# NFC_Access_NFC_Reader_R00.net
KiCad netlist of a schematic drawn in Altium Designer
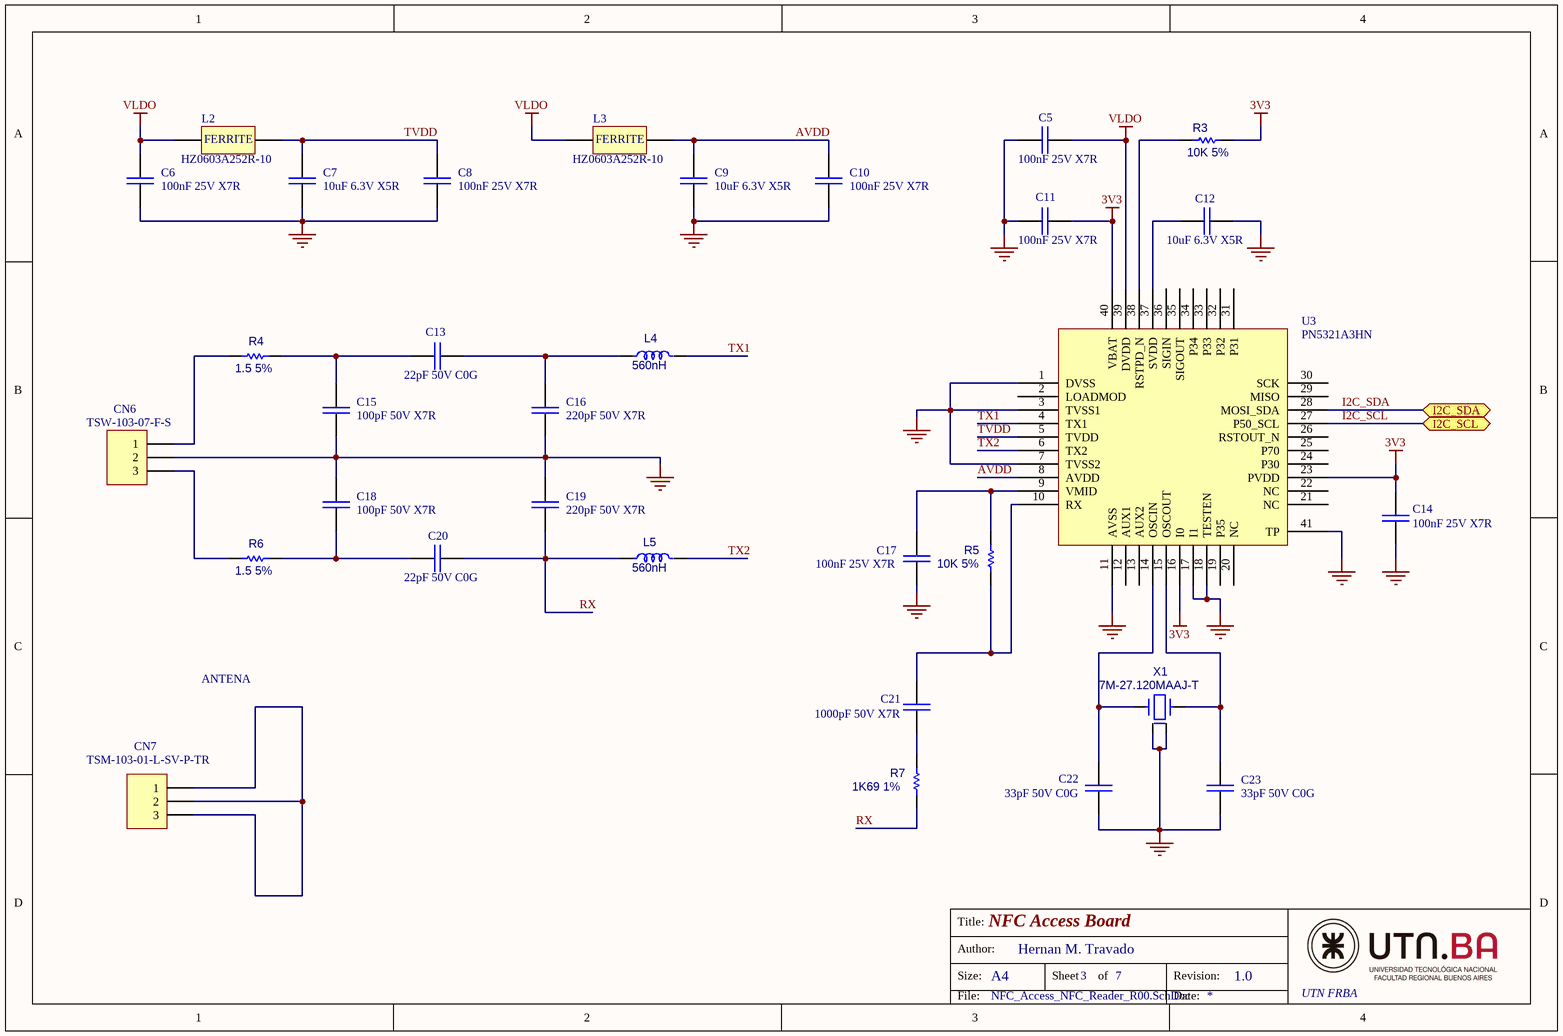
[diagram p0: NFC_Access_NFC_Reader_R00.SchDoc]

(export (version "E")
  (design (tool "Eeschema 10.0.6"))
  (components
    (comp (ref "C5")
      (value "100nF 25V X7R")
      (footprint "C_0603")
      (description "Ceramic Capacitor\r\n1276-1018-2-ND")
      (libsource (lib "NFC_Access_Lib") (part "Ceramic capacitor"))
    )
    (comp (ref "C6")
      (value "100nF 25V X7R")
      (footprint "C_0603")
      (description "Ceramic Capacitor\r\n1276-1018-2-ND")
      (libsource (lib "NFC_Access_Lib") (part "Ceramic capacitor"))
    )
    (comp (ref "C7")
      (value "10uF 6.3V X5R")
      (footprint "C_0603")
      (description "Ceramic Capacitor\r\n1276-1119-2-ND")
      (libsource (lib "NFC_Access_Lib") (part "Ceramic capacitor"))
    )
    (comp (ref "C8")
      (value "100nF 25V X7R")
      (footprint "C_0603")
      (description "Ceramic Capacitor\r\n1276-1018-2-ND")
      (libsource (lib "NFC_Access_Lib") (part "Ceramic capacitor"))
    )
    (comp (ref "C9")
      (value "10uF 6.3V X5R")
      (footprint "C_0603")
      (description "Ceramic Capacitor\r\n1276-1119-2-ND")
      (libsource (lib "NFC_Access_Lib") (part "Ceramic capacitor"))
    )
    (comp (ref "C10")
      (value "100nF 25V X7R")
      (footprint "C_0603")
      (description "Ceramic Capacitor\r\n1276-1018-2-ND")
      (libsource (lib "NFC_Access_Lib") (part "Ceramic capacitor"))
    )
    (comp (ref "C11")
      (value "100nF 25V X7R")
      (footprint "C_0603")
      (description "Ceramic Capacitor\r\n1276-1018-2-ND")
      (libsource (lib "NFC_Access_Lib") (part "Ceramic capacitor"))
    )
    (comp (ref "C12")
      (value "10uF 6.3V X5R")
      (footprint "C_0603")
      (description "Ceramic Capacitor\r\n1276-1119-2-ND")
      (libsource (lib "NFC_Access_Lib") (part "Ceramic capacitor"))
    )
    (comp (ref "C13")
      (value "22pF 50V C0G")
      (footprint "C_0603")
      (description "Ceramic Capacitor\r\n1276-2228-2-ND")
      (libsource (lib "NFC_Access_Lib") (part "Ceramic capacitor"))
    )
    (comp (ref "C14")
      (value "100nF 25V X7R")
      (footprint "C_0603")
      (description "Ceramic Capacitor\r\n1276-1018-2-ND")
      (libsource (lib "NFC_Access_Lib") (part "Ceramic capacitor"))
    )
    (comp (ref "C15")
      (value "100pF 50V X7R")
      (footprint "C_0603")
      (description "Ceramic Capacitor\r\n1276-1908-2-ND")
      (libsource (lib "NFC_Access_Lib") (part "Ceramic capacitor"))
    )
    (comp (ref "C16")
      (value "220pF 50V X7R")
      (footprint "C_0603")
      (description "Ceramic Capacitor\r\n1276-1986-2-ND")
      (libsource (lib "NFC_Access_Lib") (part "Ceramic capacitor"))
    )
    (comp (ref "C17")
      (value "100nF 25V X7R")
      (footprint "C_0603")
      (description "Ceramic Capacitor\r\n1276-1018-2-ND")
      (libsource (lib "NFC_Access_Lib") (part "Ceramic capacitor"))
    )
    (comp (ref "C18")
      (value "100pF 50V X7R")
      (footprint "C_0603")
      (description "Ceramic Capacitor\r\n1276-1908-2-ND")
      (libsource (lib "NFC_Access_Lib") (part "Ceramic capacitor"))
    )
    (comp (ref "C19")
      (value "220pF 50V X7R")
      (footprint "C_0603")
      (description "Ceramic Capacitor\r\n1276-1986-2-ND")
      (libsource (lib "NFC_Access_Lib") (part "Ceramic capacitor"))
    )
    (comp (ref "C20")
      (value "22pF 50V C0G")
      (footprint "C_0603")
      (description "Ceramic Capacitor\r\n1276-2228-2-ND")
      (libsource (lib "NFC_Access_Lib") (part "Ceramic capacitor"))
    )
    (comp (ref "C21")
      (value "1000pF 50V X7R")
      (footprint "C_0603")
      (description "Ceramic Capacitor\r\n1276-1018-2-ND")
      (libsource (lib "NFC_Access_Lib") (part "Ceramic capacitor"))
    )
    (comp (ref "C22")
      (value "33pF 50V C0G")
      (footprint "C_0603")
      (description "Ceramic Capacitor\r\n1276-1070-2-ND")
      (libsource (lib "NFC_Access_Lib") (part "Ceramic capacitor"))
    )
    (comp (ref "C23")
      (value "33pF 50V C0G")
      (footprint "C_0603")
      (description "Ceramic Capacitor\r\n1276-1070-2-ND")
      (libsource (lib "NFC_Access_Lib") (part "Ceramic capacitor"))
    )
    (comp (ref "CN6")
      (value "TSW-103-07-F-S")
      (footprint "Header_M_1x3_0.1")
      (description "CONN HEADER VERT 3POS 2.54MM\r\nSAM8995-ND")
      (libsource (lib "NFC_Access_Lib") (part "CONN_03P"))
    )
    (comp (ref "CN7")
      (value "TSM-103-01-L-SV-P-TR")
      (footprint "HEADER_M_1x3_0.1\"_SMD")
      (description "CONN HEADER SMD 3POS 2.54MM\r\nSAM13281TR-ND")
      (libsource (lib "NFC_Access_Lib") (part "CONN_03P"))
    )
    (comp (ref "L2")
      (value "HZ0603A252R-10")
      (footprint "F_0603")
      (description "Ferrite Bead\r\n240-2561-2-ND")
      (libsource (lib "NFC_Access_Lib") (part "FERRITE"))
    )
    (comp (ref "L3")
      (value "HZ0603A252R-10")
      (footprint "F_0603")
      (description "Ferrite Bead\r\n240-2561-2-ND")
      (libsource (lib "NFC_Access_Lib") (part "FERRITE"))
    )
    (comp (ref "L4")
      (value "560nH")
      (footprint "I_0603")
      (description "FIXED IND 560NH 450MA 480MOHM SM\r\n490-LQW18CNR56J0ZDTR-ND")
      (libsource (lib "NFC_Access_Lib") (part "IND"))
    )
    (comp (ref "L5")
      (value "560nH")
      (footprint "I_0603")
      (description "FIXED IND 560NH 450MA 480MOHM SM\r\n490-LQW18CNR56J0ZDTR-ND")
      (libsource (lib "NFC_Access_Lib") (part "IND"))
    )
    (comp (ref "R3")
      (value "10K 5%")
      (footprint "R_0603")
      (description "Resistor\r\nCR0603-JW-103ELFTR-ND")
      (libsource (lib "NFC_Access_Lib") (part "Res1"))
    )
    (comp (ref "R4")
      (value "1.5 5%")
      (footprint "R_0603")
      (description "Resistor SMD 0603\r\nCR0603-J/-1R5ELFTR-ND")
      (libsource (lib "NFC_Access_Lib") (part "Res1"))
    )
    (comp (ref "R5")
      (value "10K 5%")
      (footprint "R_0603")
      (description "Resistor\r\nCR0603-JW-103ELFTR-ND")
      (libsource (lib "NFC_Access_Lib") (part "Res1"))
    )
    (comp (ref "R6")
      (value "1.5 5%")
      (footprint "R_0603")
      (description "Resistor SMD 0603\r\nCR0603-J/-1R5ELFTR-ND")
      (libsource (lib "NFC_Access_Lib") (part "Res1"))
    )
    (comp (ref "R7")
      (value "1K69 1%")
      (footprint "R_0603")
      (description "Resistor\r\nCR0603-FX-1691ELFTR-ND")
      (libsource (lib "NFC_Access_Lib") (part "Res1"))
    )
    (comp (ref "U3")
      (value "PN5321A3HN")
      (footprint "QFN40G-0.5-6X6MM")
      (description "NFC Controller\r\n568-13228-ND")
      (libsource (lib "NFC_Access_Lib") (part "PN532"))
    )
    (comp (ref "X1")
      (value "7M-27.120MAAJ-T")
      (footprint "7M-4-SMD")
      (description "Crystal 4 Vias + GND 27.12 MHz\r\n887-1424-2-ND")
      (libsource (lib "NFC_Access_Lib") (part "CRYSTAL_4P"))
    )
  )
  (nets
    (net (code "1") (name "/AVDD") (class "Default")
      (node (ref "C10") (pin "1") (pinfunction "1_1") (pintype "passive"))
      (node (ref "C9") (pin "2") (pinfunction "2_2") (pintype "passive"))
      (node (ref "L3") (pin "2") (pinfunction "2_2") (pintype "passive"))
      (node (ref "U3") (pin "8") (pinfunction "AVDD_8") (pintype "passive"))
    )
    (net (code "2") (name "/I2C_SCL") (class "Default")
      (node (ref "U3") (pin "27") (pinfunction "P50_SCL_27") (pintype "passive"))
    )
    (net (code "3") (name "/I2C_SDA") (class "Default")
      (node (ref "U3") (pin "28") (pinfunction "MOSI_SDA_28") (pintype "passive"))
    )
    (net (code "4") (name "/RX") (class "Default")
      (node (ref "C19") (pin "2") (pinfunction "2_2") (pintype "passive"))
      (node (ref "C20") (pin "2") (pinfunction "2_2") (pintype "passive"))
      (node (ref "L5") (pin "1") (pinfunction "1_1") (pintype "passive"))
      (node (ref "R7") (pin "2") (pinfunction "2_2") (pintype "passive"))
    )
    (net (code "5") (name "/TVDD") (class "Default")
      (node (ref "C7") (pin "2") (pinfunction "2_2") (pintype "passive"))
      (node (ref "C8") (pin "1") (pinfunction "1_1") (pintype "passive"))
      (node (ref "L2") (pin "2") (pinfunction "2_2") (pintype "passive"))
      (node (ref "U3") (pin "5") (pinfunction "TVDD_5") (pintype "passive"))
    )
    (net (code "6") (name "/TX1") (class "Default")
      (node (ref "L4") (pin "2") (pinfunction "2_2") (pintype "passive"))
      (node (ref "U3") (pin "4") (pinfunction "TX1_4") (pintype "passive"))
    )
    (net (code "7") (name "/TX2") (class "Default")
      (node (ref "L5") (pin "2") (pinfunction "2_2") (pintype "passive"))
      (node (ref "U3") (pin "6") (pinfunction "TX2_6") (pintype "passive"))
    )
    (net (code "8") (name "3V3") (class "Default")
      (node (ref "C11") (pin "1") (pinfunction "1_1") (pintype "passive"))
      (node (ref "C14") (pin "1") (pinfunction "1_1") (pintype "passive"))
      (node (ref "R3") (pin "1") (pinfunction "1_1") (pintype "passive"))
      (node (ref "U3") (pin "16") (pinfunction "I0_16") (pintype "passive"))
      (node (ref "U3") (pin "23") (pinfunction "PVDD_23") (pintype "passive"))
      (node (ref "U3") (pin "40") (pinfunction "VBAT_40") (pintype "passive"))
    )
    (net (code "9") (name "GND") (class "Default")
      (node (ref "C10") (pin "2") (pinfunction "2_2") (pintype "passive"))
      (node (ref "C11") (pin "2") (pinfunction "2_2") (pintype "passive"))
      (node (ref "C12") (pin "2") (pinfunction "2_2") (pintype "passive"))
      (node (ref "C14") (pin "2") (pinfunction "2_2") (pintype "passive"))
      (node (ref "C15") (pin "2") (pinfunction "2_2") (pintype "passive"))
      (node (ref "C16") (pin "2") (pinfunction "2_2") (pintype "passive"))
      (node (ref "C17") (pin "2") (pinfunction "2_2") (pintype "passive"))
      (node (ref "C18") (pin "1") (pinfunction "1_1") (pintype "passive"))
      (node (ref "C19") (pin "1") (pinfunction "1_1") (pintype "passive"))
      (node (ref "C22") (pin "2") (pinfunction "2_2") (pintype "passive"))
      (node (ref "C23") (pin "2") (pinfunction "2_2") (pintype "passive"))
      (node (ref "C5") (pin "2") (pinfunction "2_2") (pintype "passive"))
      (node (ref "C6") (pin "2") (pinfunction "2_2") (pintype "passive"))
      (node (ref "C7") (pin "1") (pinfunction "1_1") (pintype "passive"))
      (node (ref "C8") (pin "2") (pinfunction "2_2") (pintype "passive"))
      (node (ref "C9") (pin "1") (pinfunction "1_1") (pintype "passive"))
      (node (ref "CN6") (pin "2") (pinfunction "2_2") (pintype "passive"))
      (node (ref "U3") (pin "1") (pinfunction "DVSS_1") (pintype "passive"))
      (node (ref "U3") (pin "11") (pinfunction "AVSS_11") (pintype "passive"))
      (node (ref "U3") (pin "17") (pinfunction "I1_17") (pintype "passive"))
      (node (ref "U3") (pin "18") (pinfunction "TESTEN_18") (pintype "passive"))
      (node (ref "U3") (pin "3") (pinfunction "TVSS1_3") (pintype "passive"))
      (node (ref "U3") (pin "41") (pinfunction "TP_41") (pintype "passive"))
      (node (ref "U3") (pin "7") (pinfunction "TVSS2_7") (pintype "passive"))
      (node (ref "X1") (pin "2") (pinfunction "2_2") (pintype "passive"))
      (node (ref "X1") (pin "4") (pinfunction "4_4") (pintype "passive"))
    )
    (net (code "10") (name "Net-(C13-Pad1)") (class "Default")
      (node (ref "C13") (pin "1") (pinfunction "1_1") (pintype "passive"))
      (node (ref "C15") (pin "1") (pinfunction "1_1") (pintype "passive"))
      (node (ref "R4") (pin "2") (pinfunction "2_2") (pintype "passive"))
    )
    (net (code "11") (name "Net-(C13-Pad2)") (class "Default")
      (node (ref "C13") (pin "2") (pinfunction "2_2") (pintype "passive"))
      (node (ref "C16") (pin "1") (pinfunction "1_1") (pintype "passive"))
      (node (ref "L4") (pin "1") (pinfunction "1_1") (pintype "passive"))
    )
    (net (code "12") (name "Net-(C18-Pad2)") (class "Default")
      (node (ref "C18") (pin "2") (pinfunction "2_2") (pintype "passive"))
      (node (ref "C20") (pin "1") (pinfunction "1_1") (pintype "passive"))
      (node (ref "R6") (pin "2") (pinfunction "2_2") (pintype "passive"))
    )
    (net (code "13") (name "Net-(C21-Pad2)") (class "Default")
      (node (ref "C21") (pin "2") (pinfunction "2_2") (pintype "passive"))
      (node (ref "R7") (pin "1") (pinfunction "1_1") (pintype "passive"))
    )
    (net (code "14") (name "Net-(CN6-Pad1)") (class "Default")
      (node (ref "CN6") (pin "1") (pinfunction "1_1") (pintype "passive"))
      (node (ref "R4") (pin "1") (pinfunction "1_1") (pintype "passive"))
    )
    (net (code "15") (name "Net-(CN6-Pad3)") (class "Default")
      (node (ref "CN6") (pin "3") (pinfunction "3_3") (pintype "passive"))
      (node (ref "R6") (pin "1") (pinfunction "1_1") (pintype "passive"))
    )
    (net (code "16") (name "Net-(CN7-Pad1)") (class "Default")
      (node (ref "CN7") (pin "1") (pinfunction "1_1") (pintype "passive"))
      (node (ref "CN7") (pin "2") (pinfunction "2_2") (pintype "passive"))
      (node (ref "CN7") (pin "3") (pinfunction "3_3") (pintype "passive"))
    )
    (net (code "17") (name "Net-(U3-OSCIN)") (class "Default")
      (node (ref "C22") (pin "1") (pinfunction "1_1") (pintype "passive"))
      (node (ref "U3") (pin "14") (pinfunction "OSCIN_14") (pintype "passive"))
      (node (ref "X1") (pin "3") (pinfunction "3_3") (pintype "passive"))
    )
    (net (code "18") (name "Net-(U3-OSCOUT)") (class "Default")
      (node (ref "C23") (pin "1") (pinfunction "1_1") (pintype "passive"))
      (node (ref "U3") (pin "15") (pinfunction "OSCOUT_15") (pintype "passive"))
      (node (ref "X1") (pin "1") (pinfunction "1_1") (pintype "passive"))
    )
    (net (code "19") (name "Net-(U3-RSTPD_N)") (class "Default")
      (node (ref "R3") (pin "2") (pinfunction "2_2") (pintype "passive"))
      (node (ref "U3") (pin "38") (pinfunction "RSTPD_N_38") (pintype "passive"))
    )
    (net (code "20") (name "Net-(U3-RX)") (class "Default")
      (node (ref "C21") (pin "1") (pinfunction "1_1") (pintype "passive"))
      (node (ref "R5") (pin "2") (pinfunction "2_2") (pintype "passive"))
      (node (ref "U3") (pin "10") (pinfunction "RX_10") (pintype "passive"))
    )
    (net (code "21") (name "Net-(U3-SVDD)") (class "Default")
      (node (ref "C12") (pin "1") (pinfunction "1_1") (pintype "passive"))
      (node (ref "U3") (pin "37") (pinfunction "SVDD_37") (pintype "passive"))
    )
    (net (code "22") (name "Net-(U3-VMID)") (class "Default")
      (node (ref "C17") (pin "1") (pinfunction "1_1") (pintype "passive"))
      (node (ref "R5") (pin "1") (pinfunction "1_1") (pintype "passive"))
      (node (ref "U3") (pin "9") (pinfunction "VMID_9") (pintype "passive"))
    )
    (net (code "23") (name "VLDO") (class "Default")
      (node (ref "C5") (pin "1") (pinfunction "1_1") (pintype "passive"))
      (node (ref "C6") (pin "1") (pinfunction "1_1") (pintype "passive"))
      (node (ref "L2") (pin "1") (pinfunction "2_1") (pintype "passive"))
      (node (ref "L3") (pin "1") (pinfunction "2_1") (pintype "passive"))
      (node (ref "U3") (pin "39") (pinfunction "DVDD_39") (pintype "passive"))
    )
    (net (code "24") (name "unconnected-(U3-AUX1-Pad12)") (class "Default")
      (node (ref "U3") (pin "12") (pinfunction "AUX1_12") (pintype "passive"))
    )
    (net (code "25") (name "unconnected-(U3-AUX2-Pad13)") (class "Default")
      (node (ref "U3") (pin "13") (pinfunction "AUX2_13") (pintype "passive"))
    )
    (net (code "26") (name "unconnected-(U3-LOADMOD-Pad2)") (class "Default")
      (node (ref "U3") (pin "2") (pinfunction "LOADMOD_2") (pintype "passive"))
    )
    (net (code "27") (name "unconnected-(U3-MISO-Pad29)") (class "Default")
      (node (ref "U3") (pin "29") (pinfunction "MISO_29") (pintype "passive"))
    )
    (net (code "28") (name "unconnected-(U3-NC-Pad20)") (class "Default")
      (node (ref "U3") (pin "20") (pinfunction "NC_20") (pintype "passive"))
    )
    (net (code "29") (name "unconnected-(U3-NC-Pad21)") (class "Default")
      (node (ref "U3") (pin "21") (pinfunction "NC_21") (pintype "passive"))
    )
    (net (code "30") (name "unconnected-(U3-NC-Pad22)") (class "Default")
      (node (ref "U3") (pin "22") (pinfunction "NC_22") (pintype "passive"))
    )
    (net (code "31") (name "unconnected-(U3-P30-Pad24)") (class "Default")
      (node (ref "U3") (pin "24") (pinfunction "P30_24") (pintype "passive"))
    )
    (net (code "32") (name "unconnected-(U3-P31-Pad31)") (class "Default")
      (node (ref "U3") (pin "31") (pinfunction "P31_31") (pintype "passive"))
    )
    (net (code "33") (name "unconnected-(U3-P32-Pad32)") (class "Default")
      (node (ref "U3") (pin "32") (pinfunction "P32_32") (pintype "passive"))
    )
    (net (code "34") (name "unconnected-(U3-P33-Pad33)") (class "Default")
      (node (ref "U3") (pin "33") (pinfunction "P33_33") (pintype "passive"))
    )
    (net (code "35") (name "unconnected-(U3-P34-Pad34)") (class "Default")
      (node (ref "U3") (pin "34") (pinfunction "P34_34") (pintype "passive"))
    )
    (net (code "36") (name "unconnected-(U3-P35-Pad19)") (class "Default")
      (node (ref "U3") (pin "19") (pinfunction "P35_19") (pintype "passive"))
    )
    (net (code "37") (name "unconnected-(U3-P70-Pad25)") (class "Default")
      (node (ref "U3") (pin "25") (pinfunction "P70_25") (pintype "passive"))
    )
    (net (code "38") (name "unconnected-(U3-RSTOUT_N-Pad26)") (class "Default")
      (node (ref "U3") (pin "26") (pinfunction "RSTOUT_N_26") (pintype "passive"))
    )
    (net (code "39") (name "unconnected-(U3-SCK-Pad30)") (class "Default")
      (node (ref "U3") (pin "30") (pinfunction "SCK_30") (pintype "passive"))
    )
    (net (code "40") (name "unconnected-(U3-SIGIN-Pad36)") (class "Default")
      (node (ref "U3") (pin "36") (pinfunction "SIGIN_36") (pintype "passive"))
    )
    (net (code "41") (name "unconnected-(U3-SIGOUT-Pad35)") (class "Default")
      (node (ref "U3") (pin "35") (pinfunction "SIGOUT_35") (pintype "passive"))
    )
  )
)
